# MC33797.net
KiCad netlist of a schematic drawn in Altium Designer
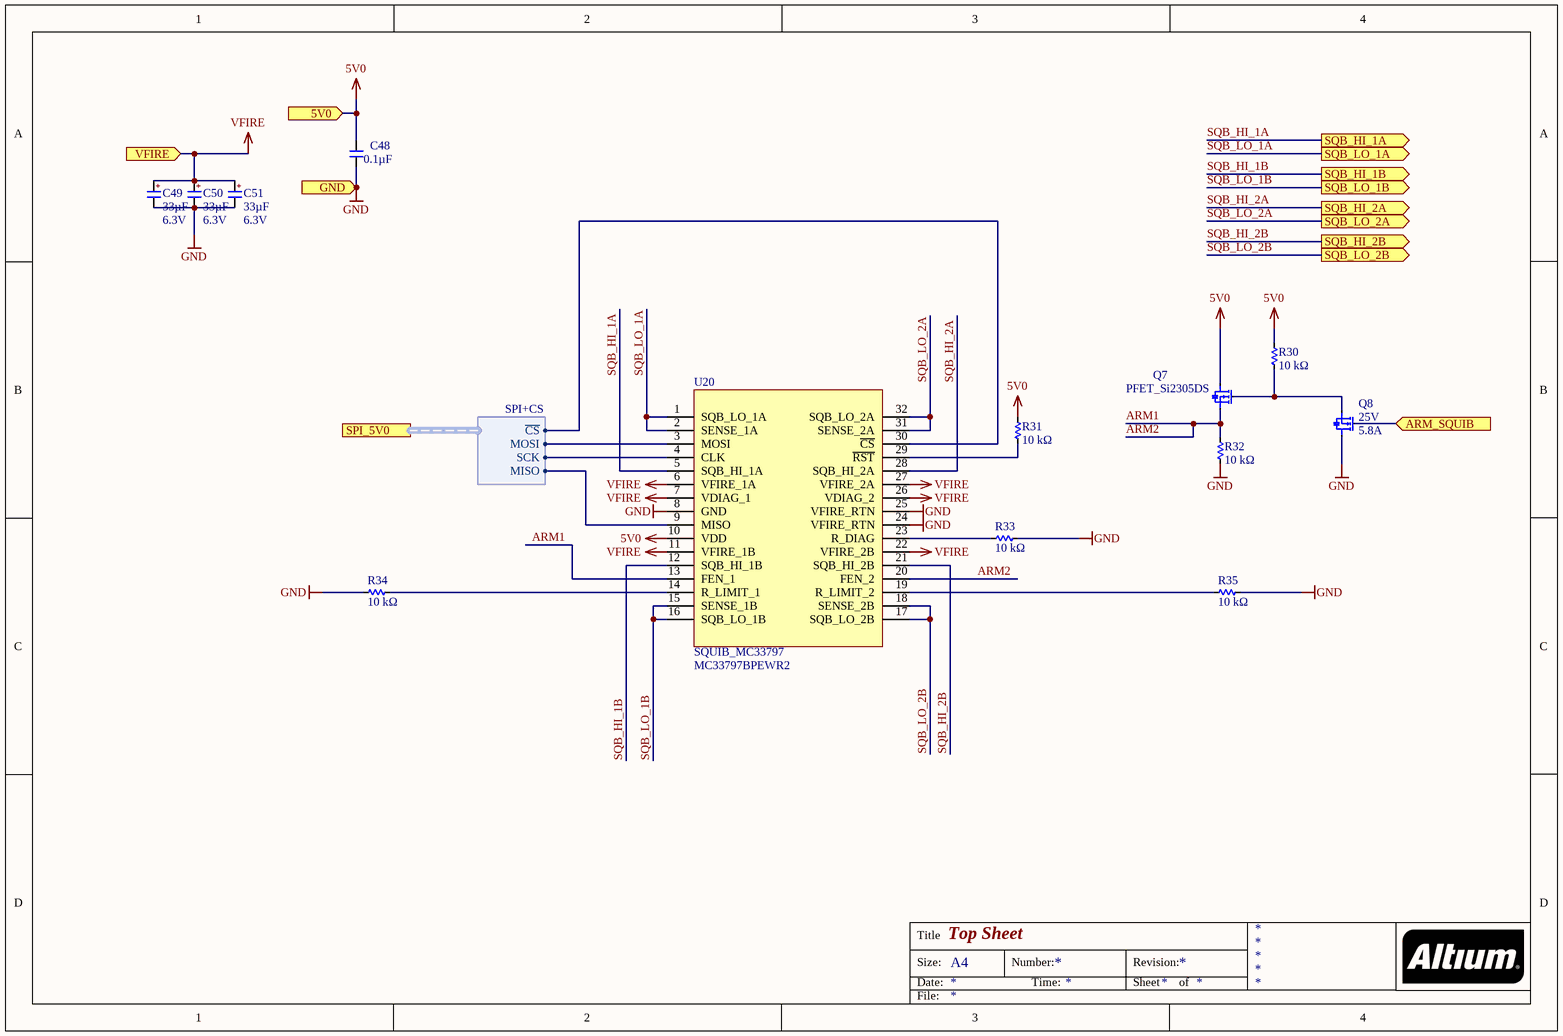
[diagram p0: MC33797.SchDoc]

(export (version "E")
  (design (tool "Eeschema 10.0.6"))
  (components
    (comp (ref "C48")
      (value "CAP_CER_100NF_100V")
      (footprint "C0603")
      (description "CAP CER 0.1UF 100V X7S 0603")
      (fields
        (field (name "MANUFACTURER") "TDK Corporation")
        (field (name "TOLERANCE") "±10%")
        (field (name "CAPACITANCE") "0.1µF")
      )
      (libsource (lib "Stanford Student Space Initiative") (part "Symbol"))
    )
    (comp (ref "C49")
      (value "CAP_TANT_33UF")
      (footprint "C1206P")
      (fields
        (field (name "MANUFACTURER") "AVX Corporation")
        (field (name "MANUFACTURER PART NUMBER") "TPSA336K006R0600")
        (field (name "TOLERANCE") "±10%")
        (field (name "CAPACITANCE") "33µF")
        (field (name "VOLTAGE - RATED") "6.3V")
      )
      (libsource (lib "Stanford Student Space Initiative") (part "CAP_TANT_33UF"))
    )
    (comp (ref "C50")
      (value "CAP_TANT_33UF")
      (footprint "C1206P")
      (fields
        (field (name "MANUFACTURER") "AVX Corporation")
        (field (name "MANUFACTURER PART NUMBER") "TPSA336K006R0600")
        (field (name "TOLERANCE") "±10%")
        (field (name "CAPACITANCE") "33µF")
        (field (name "VOLTAGE - RATED") "6.3V")
      )
      (libsource (lib "Stanford Student Space Initiative") (part "CAP_TANT_33UF"))
    )
    (comp (ref "C51")
      (value "CAP_TANT_33UF")
      (footprint "C1206P")
      (fields
        (field (name "MANUFACTURER") "AVX Corporation")
        (field (name "MANUFACTURER PART NUMBER") "TPSA336K006R0600")
        (field (name "TOLERANCE") "±10%")
        (field (name "CAPACITANCE") "33µF")
        (field (name "VOLTAGE - RATED") "6.3V")
      )
      (libsource (lib "Stanford Student Space Initiative") (part "CAP_TANT_33UF"))
    )
    (comp (ref "Q7")
      (value "PFET_Si2305DS")
      (footprint "3SOT23")
      (description "MOSFET P-CH")
      (libsource (lib "Stanford Student Space Initiative") (part "PFET_Si2305DS"))
    )
    (comp (ref "Q8")
      (value "NFET_IRFML8244TRPBF")
      (footprint "3SOT23")
      (description "MOSFET N-CH 25V 5.8A SOT23")
      (fields
        (field (name "MANUFACTURER") "International Rectifier")
        (field (name "MANUFACTURER PART NUMBER") "IRFML8244TRPBF")
        (field (name "DRAIN TO SOURCE VOLTAGE (VDSS)") "25V")
        (field (name "CURRENT - CONTINUOUS DRAIN (ID) @ 25° C") "5.8A")
      )
      (libsource (lib "") (part "Symbol_1"))
    )
    (comp (ref "R30")
      (value "311-10.0KHRCT-ND")
      (footprint "R0603")
      (description "RES SMD 10K OHM 1% 1/10W 0603")
      (fields
        (field (name "RESISTANCE") "10 kΩ")
        (field (name "MANUFACTURER PART NUMBER") "RC0603FR-0710KL")
        (field (name "MANUFACTURER") "Yageo")
      )
      (libsource (lib "Stanford Student Space Initiative") (part "__template_resistor"))
    )
    (comp (ref "R31")
      (value "311-10.0KHRCT-ND")
      (footprint "R0603")
      (description "RES SMD 10K OHM 1% 1/10W 0603")
      (fields
        (field (name "RESISTANCE") "10 kΩ")
        (field (name "MANUFACTURER PART NUMBER") "RC0603FR-0710KL")
        (field (name "MANUFACTURER") "Yageo")
      )
      (libsource (lib "Stanford Student Space Initiative") (part "__template_resistor"))
    )
    (comp (ref "R32")
      (value "311-10.0KHRCT-ND")
      (footprint "R0603")
      (description "RES SMD 10K OHM 1% 1/10W 0603")
      (fields
        (field (name "RESISTANCE") "10 kΩ")
        (field (name "MANUFACTURER PART NUMBER") "RC0603FR-0710KL")
        (field (name "MANUFACTURER") "Yageo")
      )
      (libsource (lib "Stanford Student Space Initiative") (part "__template_resistor"))
    )
    (comp (ref "R33")
      (value "311-10.0KHRCT-ND")
      (footprint "R0603")
      (description "RES SMD 10K OHM 1% 1/10W 0603")
      (fields
        (field (name "RESISTANCE") "10 kΩ")
        (field (name "MANUFACTURER PART NUMBER") "RC0603FR-0710KL")
        (field (name "MANUFACTURER") "Yageo")
      )
      (libsource (lib "Stanford Student Space Initiative") (part "__template_resistor"))
    )
    (comp (ref "R34")
      (value "311-10.0KHRCT-ND")
      (footprint "R0603")
      (description "RES SMD 10K OHM 1% 1/10W 0603")
      (fields
        (field (name "RESISTANCE") "10 kΩ")
        (field (name "MANUFACTURER PART NUMBER") "RC0603FR-0710KL")
        (field (name "MANUFACTURER") "Yageo")
      )
      (libsource (lib "Stanford Student Space Initiative") (part "__template_resistor"))
    )
    (comp (ref "R35")
      (value "311-10.0KHRCT-ND")
      (footprint "R0603")
      (description "RES SMD 10K OHM 1% 1/10W 0603")
      (fields
        (field (name "RESISTANCE") "10 kΩ")
        (field (name "MANUFACTURER PART NUMBER") "RC0603FR-0710KL")
        (field (name "MANUFACTURER") "Yageo")
      )
      (libsource (lib "Stanford Student Space Initiative") (part "__template_resistor"))
    )
    (comp (ref "U20")
      (value "SQUIB_MC33797")
      (footprint "SOT1762-1")
      (fields
        (field (name "MANUFACTURER") "NXP USA Inc.")
        (field (name "MANUFACTURER PART NUMBER") "MC33797BPEWR2")
      )
      (libsource (lib "Stanford Student Space Initiative") (part "SQUIB_MC33797"))
    )
  )
  (nets
    (net (code "2") (name "/ARM1") (class "Default")
      (node (ref "Q7") (pin "2") (pintype "passive"))
      (node (ref "R32") (pin "2") (pinfunction "2_2") (pintype "passive"))
      (node (ref "U20") (pin "13") (pinfunction "FEN_1_13") (pintype "passive"))
      (node (ref "U20") (pin "20") (pinfunction "FEN_2_20") (pintype "passive"))
    )
    (net (code "3") (name "/ARM_SQUIB") (class "Default") (node (ref "Q8") (pin "1") (pintype "passive")))
    (net (code "4") (name "/MISO") (class "Default")
      (node (ref "U20") (pin "9") (pinfunction "MISO_9") (pintype "passive"))
    )
    (net (code "5") (name "/MOSI") (class "Default")
      (node (ref "U20") (pin "3") (pinfunction "MOSI_3") (pintype "passive"))
    )
    (net (code "6") (name "/SCK") (class "Default")
      (node (ref "U20") (pin "4") (pinfunction "CLK_4") (pintype "passive"))
    )
    (net (code "7") (name "/SQB_HI_1A") (class "Default")
      (node (ref "U20") (pin "5") (pinfunction "SQB_HI_1A_5") (pintype "passive"))
    )
    (net (code "8") (name "/SQB_HI_1B") (class "Default")
      (node (ref "U20") (pin "12") (pinfunction "SQB_HI_1B_12") (pintype "passive"))
    )
    (net (code "9") (name "/SQB_HI_2A") (class "Default")
      (node (ref "U20") (pin "28") (pinfunction "SQB_HI_2A_28") (pintype "passive"))
    )
    (net (code "10") (name "/SQB_HI_2B") (class "Default")
      (node (ref "U20") (pin "21") (pinfunction "SQB_HI_2B_21") (pintype "passive"))
    )
    (net (code "11") (name "/SQB_LO_1A") (class "Default")
      (node (ref "U20") (pin "1") (pinfunction "SQB_LO_1A_1") (pintype "passive"))
      (node (ref "U20") (pin "2") (pinfunction "SENSE_1A_2") (pintype "passive"))
    )
    (net (code "12") (name "/SQB_LO_1B") (class "Default")
      (node (ref "U20") (pin "15") (pinfunction "SENSE_1B_15") (pintype "passive"))
      (node (ref "U20") (pin "16") (pinfunction "SQB_LO_1B_16") (pintype "passive"))
    )
    (net (code "13") (name "/SQB_LO_2A") (class "Default")
      (node (ref "U20") (pin "31") (pinfunction "SENSE_2A_31") (pintype "passive"))
      (node (ref "U20") (pin "32") (pinfunction "SQB_LO_2A_32") (pintype "passive"))
    )
    (net (code "14") (name "/SQB_LO_2B") (class "Default")
      (node (ref "U20") (pin "17") (pinfunction "SQB_LO_2B_17") (pintype "passive"))
      (node (ref "U20") (pin "18") (pinfunction "SENSE_2B_18") (pintype "passive"))
    )
    (net (code "16") (name "/~{CS}") (class "Default")
      (node (ref "U20") (pin "30") (pinfunction "~{CS}_30") (pintype "passive"))
    )
    (net (code "17") (name "5V0") (class "Default")
      (node (ref "C48") (pin "1") (pintype "passive"))
      (node (ref "Q7") (pin "3") (pintype "passive"))
      (node (ref "R30") (pin "2") (pinfunction "2_2") (pintype "passive"))
      (node (ref "R31") (pin "2") (pinfunction "2_2") (pintype "passive"))
      (node (ref "U20") (pin "10") (pinfunction "VDD_10") (pintype "passive"))
    )
    (net (code "18") (name "GND") (class "Default")
      (node (ref "C48") (pin "2") (pintype "passive"))
      (node (ref "C49") (pin "2") (pintype "passive"))
      (node (ref "C50") (pin "2") (pintype "passive"))
      (node (ref "C51") (pin "2") (pintype "passive"))
      (node (ref "Q8") (pin "3") (pintype "passive"))
      (node (ref "R32") (pin "1") (pinfunction "1_1") (pintype "passive"))
      (node (ref "R33") (pin "2") (pinfunction "2_2") (pintype "passive"))
      (node (ref "R34") (pin "1") (pinfunction "1_1") (pintype "passive"))
      (node (ref "R35") (pin "2") (pinfunction "2_2") (pintype "passive"))
      (node (ref "U20") (pin "24") (pinfunction "VFIRE_RTN_24") (pintype "passive"))
      (node (ref "U20") (pin "25") (pinfunction "VFIRE_RTN_25") (pintype "passive"))
      (node (ref "U20") (pin "8") (pinfunction "GND_8") (pintype "passive"))
    )
    (net (code "19") (name "Net-(Q7-Pad1)") (class "Default")
      (node (ref "Q7") (pin "1") (pintype "passive"))
      (node (ref "Q8") (pin "2") (pintype "passive"))
      (node (ref "R30") (pin "1") (pinfunction "1_1") (pintype "passive"))
    )
    (net (code "20") (name "Net-(U20-R_DIAG)") (class "Default")
      (node (ref "R33") (pin "1") (pinfunction "1_1") (pintype "passive"))
      (node (ref "U20") (pin "23") (pinfunction "R_DIAG_23") (pintype "passive"))
    )
    (net (code "21") (name "Net-(U20-R_LIMIT_1)") (class "Default")
      (node (ref "R34") (pin "2") (pinfunction "2_2") (pintype "passive"))
      (node (ref "U20") (pin "14") (pinfunction "R_LIMIT_1_14") (pintype "passive"))
    )
    (net (code "22") (name "Net-(U20-R_LIMIT_2)") (class "Default")
      (node (ref "R35") (pin "1") (pinfunction "1_1") (pintype "passive"))
      (node (ref "U20") (pin "19") (pinfunction "R_LIMIT_2_19") (pintype "passive"))
    )
    (net (code "23") (name "Net-(U20-~{RST})") (class "Default")
      (node (ref "R31") (pin "1") (pinfunction "1_1") (pintype "passive"))
      (node (ref "U20") (pin "29") (pinfunction "~{RST}_29") (pintype "passive"))
    )
    (net (code "24") (name "VFIRE") (class "Default")
      (node (ref "C49") (pin "1") (pintype "passive"))
      (node (ref "C50") (pin "1") (pintype "passive"))
      (node (ref "C51") (pin "1") (pintype "passive"))
      (node (ref "U20") (pin "11") (pinfunction "VFIRE_1B_11") (pintype "passive"))
      (node (ref "U20") (pin "22") (pinfunction "VFIRE_2B_22") (pintype "passive"))
      (node (ref "U20") (pin "26") (pinfunction "VDIAG_2_26") (pintype "passive"))
      (node (ref "U20") (pin "27") (pinfunction "VFIRE_2A_27") (pintype "passive"))
      (node (ref "U20") (pin "6") (pinfunction "VFIRE_1A_6") (pintype "passive"))
      (node (ref "U20") (pin "7") (pinfunction "VDIAG_1_7") (pintype "passive"))
    )
  )
)
